# Tunnel_7button.net
KiCad netlist of a schematic drawn in EAGLE
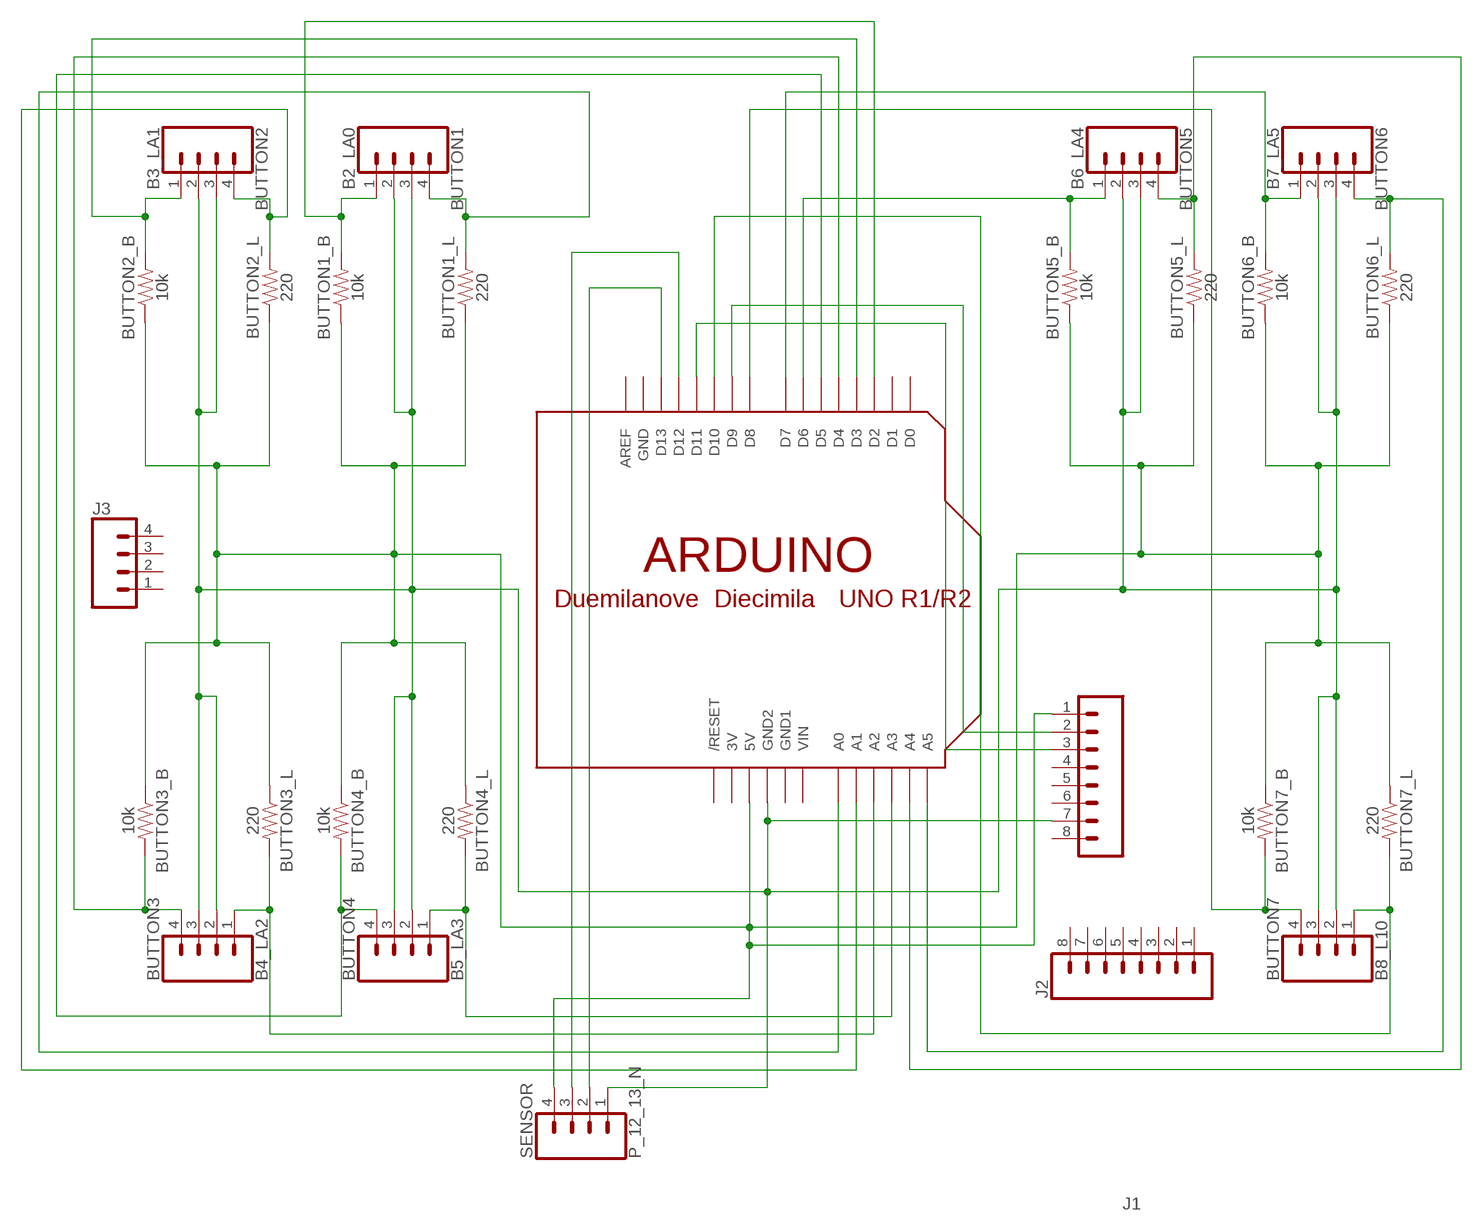
[diagram p0: schematic, sheet 1]

(export (version "E")
  (design (tool "Eeschema 10.0.6"))
  (components
    (comp (ref "BUTTON1")
      (value "B2_LA0")
      (footprint "eagle-import:1X04_LOCK")
      (libsource (lib "eagle-import") (part "CONN_04LOCK"))
    )
    (comp (ref "BUTTON1_B")
      (value "10k")
      (footprint "eagle-import:AXIAL-0.3")
      (libsource (lib "eagle-import") (part "10KOHM-HORIZ-1/4W-1%"))
    )
    (comp (ref "BUTTON1_L")
      (value "220")
      (footprint "eagle-import:AXIAL-0.3")
      (libsource (lib "eagle-import") (part "10KOHM-HORIZ-1/4W-1%"))
    )
    (comp (ref "BUTTON2")
      (value "B3_LA1")
      (footprint "eagle-import:1X04_LOCK")
      (libsource (lib "eagle-import") (part "CONN_04LOCK"))
    )
    (comp (ref "BUTTON2_B")
      (value "10k")
      (footprint "eagle-import:AXIAL-0.3")
      (libsource (lib "eagle-import") (part "10KOHM-HORIZ-1/4W-1%"))
    )
    (comp (ref "BUTTON2_L")
      (value "220")
      (footprint "eagle-import:AXIAL-0.3")
      (libsource (lib "eagle-import") (part "10KOHM-HORIZ-1/4W-1%"))
    )
    (comp (ref "BUTTON3")
      (value "B4_LA2")
      (footprint "eagle-import:1X04_LOCK")
      (libsource (lib "eagle-import") (part "CONN_04LOCK"))
    )
    (comp (ref "BUTTON3_B")
      (value "10k")
      (footprint "eagle-import:AXIAL-0.3")
      (libsource (lib "eagle-import") (part "10KOHM-HORIZ-1/4W-1%"))
    )
    (comp (ref "BUTTON3_L")
      (value "220")
      (footprint "eagle-import:AXIAL-0.3")
      (libsource (lib "eagle-import") (part "10KOHM-HORIZ-1/4W-1%"))
    )
    (comp (ref "BUTTON4")
      (value "B5_LA3")
      (footprint "eagle-import:1X04_LOCK")
      (libsource (lib "eagle-import") (part "CONN_04LOCK"))
    )
    (comp (ref "BUTTON4_B")
      (value "10k")
      (footprint "eagle-import:AXIAL-0.3")
      (libsource (lib "eagle-import") (part "10KOHM-HORIZ-1/4W-1%"))
    )
    (comp (ref "BUTTON4_L")
      (value "220")
      (footprint "eagle-import:AXIAL-0.3")
      (libsource (lib "eagle-import") (part "10KOHM-HORIZ-1/4W-1%"))
    )
    (comp (ref "BUTTON5")
      (value "B6_LA4")
      (footprint "eagle-import:1X04_LOCK")
      (libsource (lib "eagle-import") (part "CONN_04LOCK"))
    )
    (comp (ref "BUTTON5_B")
      (value "10k")
      (footprint "eagle-import:AXIAL-0.3")
      (libsource (lib "eagle-import") (part "10KOHM-HORIZ-1/4W-1%"))
    )
    (comp (ref "BUTTON5_L")
      (value "220")
      (footprint "eagle-import:AXIAL-0.3")
      (libsource (lib "eagle-import") (part "10KOHM-HORIZ-1/4W-1%"))
    )
    (comp (ref "BUTTON6")
      (value "B7_LA5")
      (footprint "eagle-import:1X04_LOCK")
      (libsource (lib "eagle-import") (part "CONN_04LOCK"))
    )
    (comp (ref "BUTTON6_B")
      (value "10k")
      (footprint "eagle-import:AXIAL-0.3")
      (libsource (lib "eagle-import") (part "10KOHM-HORIZ-1/4W-1%"))
    )
    (comp (ref "BUTTON6_L")
      (value "220")
      (footprint "eagle-import:AXIAL-0.3")
      (libsource (lib "eagle-import") (part "10KOHM-HORIZ-1/4W-1%"))
    )
    (comp (ref "BUTTON7")
      (value "B8_L10")
      (footprint "eagle-import:1X04_LOCK")
      (libsource (lib "eagle-import") (part "CONN_04LOCK"))
    )
    (comp (ref "BUTTON7_B")
      (value "10k")
      (footprint "eagle-import:AXIAL-0.3")
      (libsource (lib "eagle-import") (part "10KOHM-HORIZ-1/4W-1%"))
    )
    (comp (ref "BUTTON7_L")
      (value "220")
      (footprint "eagle-import:AXIAL-0.3")
      (libsource (lib "eagle-import") (part "10KOHM-HORIZ-1/4W-1%"))
    )
    (comp (ref "J1")
      (value "CONN_08LOCK")
      (footprint "eagle-import:1X08_LOCK")
      (libsource (lib "eagle-import") (part "CONN_08LOCK"))
    )
    (comp (ref "J2")
      (value "CONN_08LOCK")
      (footprint "eagle-import:1X08_LOCK")
      (libsource (lib "eagle-import") (part "CONN_08LOCK"))
    )
    (comp (ref "J3")
      (value "CONN_04LOCK")
      (footprint "eagle-import:1X04_LOCK")
      (libsource (lib "eagle-import") (part "CONN_04LOCK"))
    )
    (comp (ref "SENSOR")
      (value "P_12_13_N")
      (footprint "eagle-import:1X04_LOCK")
      (libsource (lib "eagle-import") (part "CONN_04LOCK"))
    )
    (comp (ref "U$1")
      (value "ARDUINO-BPLACE")
      (footprint "eagle-import:ARDUINO-BPLACE")
      (libsource (lib "eagle-import") (part "ARDUINO-BPLACE"))
    )
  )
  (nets
    (net (code "1") (name "/3V") (class "Default")
      (node (ref "U$1") (pin "3V") (pinfunction "3V_3V") (pintype "power_in"))
    )
    (net (code "2") (name "/GND") (class "Default")
      (node (ref "U$1") (pin "GND") (pinfunction "GND_GND") (pintype "power_in"))
    )
    (net (code "3") (name "/GND1") (class "Default")
      (node (ref "U$1") (pin "GND1") (pinfunction "GND1_GND1") (pintype "power_in"))
    )
    (net (code "4") (name "/VIN") (class "Default")
      (node (ref "U$1") (pin "VIN") (pinfunction "VIN_VIN") (pintype "power_in"))
    )
    (net (code "5") (name "Net-(BUTTON1-Pad2)") (class "Default")
      (node (ref "BUTTON1") (pin "2") (pinfunction "2_2") (pintype "passive"))
      (node (ref "BUTTON1") (pin "3") (pinfunction "3_3") (pintype "passive"))
      (node (ref "BUTTON2") (pin "2") (pinfunction "2_2") (pintype "passive"))
      (node (ref "BUTTON2") (pin "3") (pinfunction "3_3") (pintype "passive"))
      (node (ref "BUTTON3") (pin "2") (pinfunction "2_2") (pintype "passive"))
      (node (ref "BUTTON3") (pin "3") (pinfunction "3_3") (pintype "passive"))
      (node (ref "BUTTON4") (pin "2") (pinfunction "2_2") (pintype "passive"))
      (node (ref "BUTTON4") (pin "3") (pinfunction "3_3") (pintype "passive"))
      (node (ref "BUTTON5") (pin "2") (pinfunction "2_2") (pintype "passive"))
      (node (ref "BUTTON5") (pin "3") (pinfunction "3_3") (pintype "passive"))
      (node (ref "BUTTON6") (pin "2") (pinfunction "2_2") (pintype "passive"))
      (node (ref "BUTTON6") (pin "3") (pinfunction "3_3") (pintype "passive"))
      (node (ref "BUTTON7") (pin "2") (pinfunction "2_2") (pintype "passive"))
      (node (ref "BUTTON7") (pin "3") (pinfunction "3_3") (pintype "passive"))
      (node (ref "J1") (pin "7") (pinfunction "7_7") (pintype "passive"))
      (node (ref "SENSOR") (pin "1") (pinfunction "1_1") (pintype "passive"))
      (node (ref "U$1") (pin "GND2") (pinfunction "GND2_GND2") (pintype "power_in"))
    )
    (net (code "6") (name "Net-(BUTTON1_B-1)") (class "Default")
      (node (ref "BUTTON1_B") (pin "P$1") (pinfunction "1_P$1") (pintype "passive"))
      (node (ref "BUTTON1_L") (pin "P$1") (pinfunction "1_P$1") (pintype "passive"))
      (node (ref "BUTTON2_B") (pin "P$1") (pinfunction "1_P$1") (pintype "passive"))
      (node (ref "BUTTON2_L") (pin "P$1") (pinfunction "1_P$1") (pintype "passive"))
      (node (ref "BUTTON3_B") (pin "P$1") (pinfunction "1_P$1") (pintype "passive"))
      (node (ref "BUTTON3_L") (pin "P$1") (pinfunction "1_P$1") (pintype "passive"))
      (node (ref "BUTTON4_B") (pin "P$1") (pinfunction "1_P$1") (pintype "passive"))
      (node (ref "BUTTON4_L") (pin "P$1") (pinfunction "1_P$1") (pintype "passive"))
      (node (ref "BUTTON5_B") (pin "P$1") (pinfunction "1_P$1") (pintype "passive"))
      (node (ref "BUTTON5_L") (pin "P$1") (pinfunction "1_P$1") (pintype "passive"))
      (node (ref "BUTTON6_B") (pin "P$1") (pinfunction "1_P$1") (pintype "passive"))
      (node (ref "BUTTON6_L") (pin "P$1") (pinfunction "1_P$1") (pintype "passive"))
      (node (ref "BUTTON7_B") (pin "P$1") (pinfunction "1_P$1") (pintype "passive"))
      (node (ref "BUTTON7_L") (pin "P$1") (pinfunction "1_P$1") (pintype "passive"))
      (node (ref "J1") (pin "1") (pinfunction "1_1") (pintype "passive"))
      (node (ref "SENSOR") (pin "4") (pinfunction "4_4") (pintype "passive"))
      (node (ref "U$1") (pin "5V") (pinfunction "5V_5V") (pintype "power_in"))
    )
    (net (code "7") (name "Net-(BUTTON1_B-2)") (class "Default")
      (node (ref "BUTTON1") (pin "1") (pinfunction "1_1") (pintype "passive"))
      (node (ref "BUTTON1_B") (pin "P$2") (pinfunction "2_P$2") (pintype "passive"))
      (node (ref "U$1") (pin "D2") (pinfunction "D2_D2") (pintype "bidirectional"))
    )
    (net (code "8") (name "Net-(BUTTON1_L-2)") (class "Default")
      (node (ref "BUTTON1") (pin "4") (pinfunction "4_4") (pintype "passive"))
      (node (ref "BUTTON1_L") (pin "P$2") (pinfunction "2_P$2") (pintype "passive"))
      (node (ref "U$1") (pin "A0") (pinfunction "A0_A0") (pintype "bidirectional"))
    )
    (net (code "9") (name "Net-(BUTTON2_B-2)") (class "Default")
      (node (ref "BUTTON2") (pin "1") (pinfunction "1_1") (pintype "passive"))
      (node (ref "BUTTON2_B") (pin "P$2") (pinfunction "2_P$2") (pintype "passive"))
      (node (ref "U$1") (pin "D3") (pinfunction "D3_D3") (pintype "bidirectional"))
    )
    (net (code "10") (name "Net-(BUTTON2_L-2)") (class "Default")
      (node (ref "BUTTON2") (pin "4") (pinfunction "4_4") (pintype "passive"))
      (node (ref "BUTTON2_L") (pin "P$2") (pinfunction "2_P$2") (pintype "passive"))
      (node (ref "U$1") (pin "A1") (pinfunction "A1_A1") (pintype "bidirectional"))
    )
    (net (code "11") (name "Net-(BUTTON3_B-2)") (class "Default")
      (node (ref "BUTTON3") (pin "4") (pinfunction "4_4") (pintype "passive"))
      (node (ref "BUTTON3_B") (pin "P$2") (pinfunction "2_P$2") (pintype "passive"))
      (node (ref "U$1") (pin "D4") (pinfunction "D4_D4") (pintype "bidirectional"))
    )
    (net (code "12") (name "Net-(BUTTON3_L-2)") (class "Default")
      (node (ref "BUTTON3") (pin "1") (pinfunction "1_1") (pintype "passive"))
      (node (ref "BUTTON3_L") (pin "P$2") (pinfunction "2_P$2") (pintype "passive"))
      (node (ref "U$1") (pin "A2") (pinfunction "A2_A2") (pintype "bidirectional"))
    )
    (net (code "13") (name "Net-(BUTTON4_B-2)") (class "Default")
      (node (ref "BUTTON4") (pin "4") (pinfunction "4_4") (pintype "passive"))
      (node (ref "BUTTON4_B") (pin "P$2") (pinfunction "2_P$2") (pintype "passive"))
      (node (ref "U$1") (pin "D5") (pinfunction "D5_D5") (pintype "bidirectional"))
    )
    (net (code "14") (name "Net-(BUTTON4_L-2)") (class "Default")
      (node (ref "BUTTON4") (pin "1") (pinfunction "1_1") (pintype "passive"))
      (node (ref "BUTTON4_L") (pin "P$2") (pinfunction "2_P$2") (pintype "passive"))
      (node (ref "U$1") (pin "A3") (pinfunction "A3_A3") (pintype "bidirectional"))
    )
    (net (code "15") (name "Net-(BUTTON5_B-2)") (class "Default")
      (node (ref "BUTTON5") (pin "1") (pinfunction "1_1") (pintype "passive"))
      (node (ref "BUTTON5_B") (pin "P$2") (pinfunction "2_P$2") (pintype "passive"))
      (node (ref "U$1") (pin "D6") (pinfunction "D6_D6") (pintype "bidirectional"))
    )
    (net (code "16") (name "Net-(BUTTON5_L-2)") (class "Default")
      (node (ref "BUTTON5") (pin "4") (pinfunction "4_4") (pintype "passive"))
      (node (ref "BUTTON5_L") (pin "P$2") (pinfunction "2_P$2") (pintype "passive"))
      (node (ref "U$1") (pin "A4") (pinfunction "A4_A4") (pintype "bidirectional"))
    )
    (net (code "17") (name "Net-(BUTTON6_B-2)") (class "Default")
      (node (ref "BUTTON6") (pin "1") (pinfunction "1_1") (pintype "passive"))
      (node (ref "BUTTON6_B") (pin "P$2") (pinfunction "2_P$2") (pintype "passive"))
      (node (ref "U$1") (pin "D7") (pinfunction "D7_D7") (pintype "bidirectional"))
    )
    (net (code "18") (name "Net-(BUTTON6_L-2)") (class "Default")
      (node (ref "BUTTON6") (pin "4") (pinfunction "4_4") (pintype "passive"))
      (node (ref "BUTTON6_L") (pin "P$2") (pinfunction "2_P$2") (pintype "passive"))
      (node (ref "U$1") (pin "A5") (pinfunction "A5_A5") (pintype "bidirectional"))
    )
    (net (code "19") (name "Net-(BUTTON7_B-2)") (class "Default")
      (node (ref "BUTTON7") (pin "4") (pinfunction "4_4") (pintype "passive"))
      (node (ref "BUTTON7_B") (pin "P$2") (pinfunction "2_P$2") (pintype "passive"))
      (node (ref "U$1") (pin "D8") (pinfunction "D8_D8") (pintype "bidirectional"))
    )
    (net (code "20") (name "Net-(BUTTON7_L-2)") (class "Default")
      (node (ref "BUTTON7") (pin "1") (pinfunction "1_1") (pintype "passive"))
      (node (ref "BUTTON7_L") (pin "P$2") (pinfunction "2_P$2") (pintype "passive"))
      (node (ref "U$1") (pin "D10") (pinfunction "D10_D10") (pintype "bidirectional"))
    )
    (net (code "21") (name "Net-(J1-Pad2)") (class "Default")
      (node (ref "J1") (pin "2") (pinfunction "2_2") (pintype "passive"))
      (node (ref "U$1") (pin "D9") (pinfunction "D9_D9") (pintype "bidirectional"))
    )
    (net (code "22") (name "Net-(J1-Pad3)") (class "Default")
      (node (ref "J1") (pin "3") (pinfunction "3_3") (pintype "passive"))
      (node (ref "U$1") (pin "D11") (pinfunction "D11_D11") (pintype "bidirectional"))
    )
    (net (code "23") (name "Net-(SENSOR-Pad2)") (class "Default")
      (node (ref "SENSOR") (pin "2") (pinfunction "2_2") (pintype "passive"))
      (node (ref "U$1") (pin "D13") (pinfunction "D13_D13") (pintype "bidirectional"))
    )
    (net (code "24") (name "Net-(SENSOR-Pad3)") (class "Default")
      (node (ref "SENSOR") (pin "3") (pinfunction "3_3") (pintype "passive"))
      (node (ref "U$1") (pin "D12") (pinfunction "D12_D12") (pintype "bidirectional"))
    )
    (net (code "25") (name "unconnected-(J1-Pad4)") (class "Default")
      (node (ref "J1") (pin "4") (pinfunction "4_4") (pintype "passive"))
    )
    (net (code "26") (name "unconnected-(J1-Pad5)") (class "Default")
      (node (ref "J1") (pin "5") (pinfunction "5_5") (pintype "passive"))
    )
    (net (code "27") (name "unconnected-(J1-Pad6)") (class "Default")
      (node (ref "J1") (pin "6") (pinfunction "6_6") (pintype "passive"))
    )
    (net (code "28") (name "unconnected-(J1-Pad8)") (class "Default")
      (node (ref "J1") (pin "8") (pinfunction "8_8") (pintype "passive"))
    )
    (net (code "29") (name "unconnected-(J2-Pad1)") (class "Default")
      (node (ref "J2") (pin "1") (pinfunction "1_1") (pintype "passive"))
    )
    (net (code "30") (name "unconnected-(J2-Pad2)") (class "Default")
      (node (ref "J2") (pin "2") (pinfunction "2_2") (pintype "passive"))
    )
    (net (code "31") (name "unconnected-(J2-Pad3)") (class "Default")
      (node (ref "J2") (pin "3") (pinfunction "3_3") (pintype "passive"))
    )
    (net (code "32") (name "unconnected-(J2-Pad4)") (class "Default")
      (node (ref "J2") (pin "4") (pinfunction "4_4") (pintype "passive"))
    )
    (net (code "33") (name "unconnected-(J2-Pad5)") (class "Default")
      (node (ref "J2") (pin "5") (pinfunction "5_5") (pintype "passive"))
    )
    (net (code "34") (name "unconnected-(J2-Pad6)") (class "Default")
      (node (ref "J2") (pin "6") (pinfunction "6_6") (pintype "passive"))
    )
    (net (code "35") (name "unconnected-(J2-Pad7)") (class "Default")
      (node (ref "J2") (pin "7") (pinfunction "7_7") (pintype "passive"))
    )
    (net (code "36") (name "unconnected-(J2-Pad8)") (class "Default")
      (node (ref "J2") (pin "8") (pinfunction "8_8") (pintype "passive"))
    )
    (net (code "37") (name "unconnected-(J3-Pad1)") (class "Default")
      (node (ref "J3") (pin "1") (pinfunction "1_1") (pintype "passive"))
    )
    (net (code "38") (name "unconnected-(J3-Pad2)") (class "Default")
      (node (ref "J3") (pin "2") (pinfunction "2_2") (pintype "passive"))
    )
    (net (code "39") (name "unconnected-(J3-Pad3)") (class "Default")
      (node (ref "J3") (pin "3") (pinfunction "3_3") (pintype "passive"))
    )
    (net (code "40") (name "unconnected-(J3-Pad4)") (class "Default")
      (node (ref "J3") (pin "4") (pinfunction "4_4") (pintype "passive"))
    )
    (net (code "41") (name "unconnected-(U$1-PadAREF)") (class "Default")
      (node (ref "U$1") (pin "AREF") (pinfunction "AREF_AREF") (pintype "bidirectional"))
    )
    (net (code "42") (name "unconnected-(U$1-PadD0)") (class "Default")
      (node (ref "U$1") (pin "D0") (pinfunction "D0_D0") (pintype "bidirectional"))
    )
    (net (code "43") (name "unconnected-(U$1-PadD1)") (class "Default")
      (node (ref "U$1") (pin "D1") (pinfunction "D1_D1") (pintype "bidirectional"))
    )
    (net (code "44") (name "unconnected-(U$1-{slash}RESET-PadRESET)") (class "Default")
      (node (ref "U$1") (pin "RESET") (pinfunction "/RESET_RESET") (pintype "bidirectional"))
    )
  )
)
